# Salida.net
KiCad netlist of a schematic drawn in Altium Designer
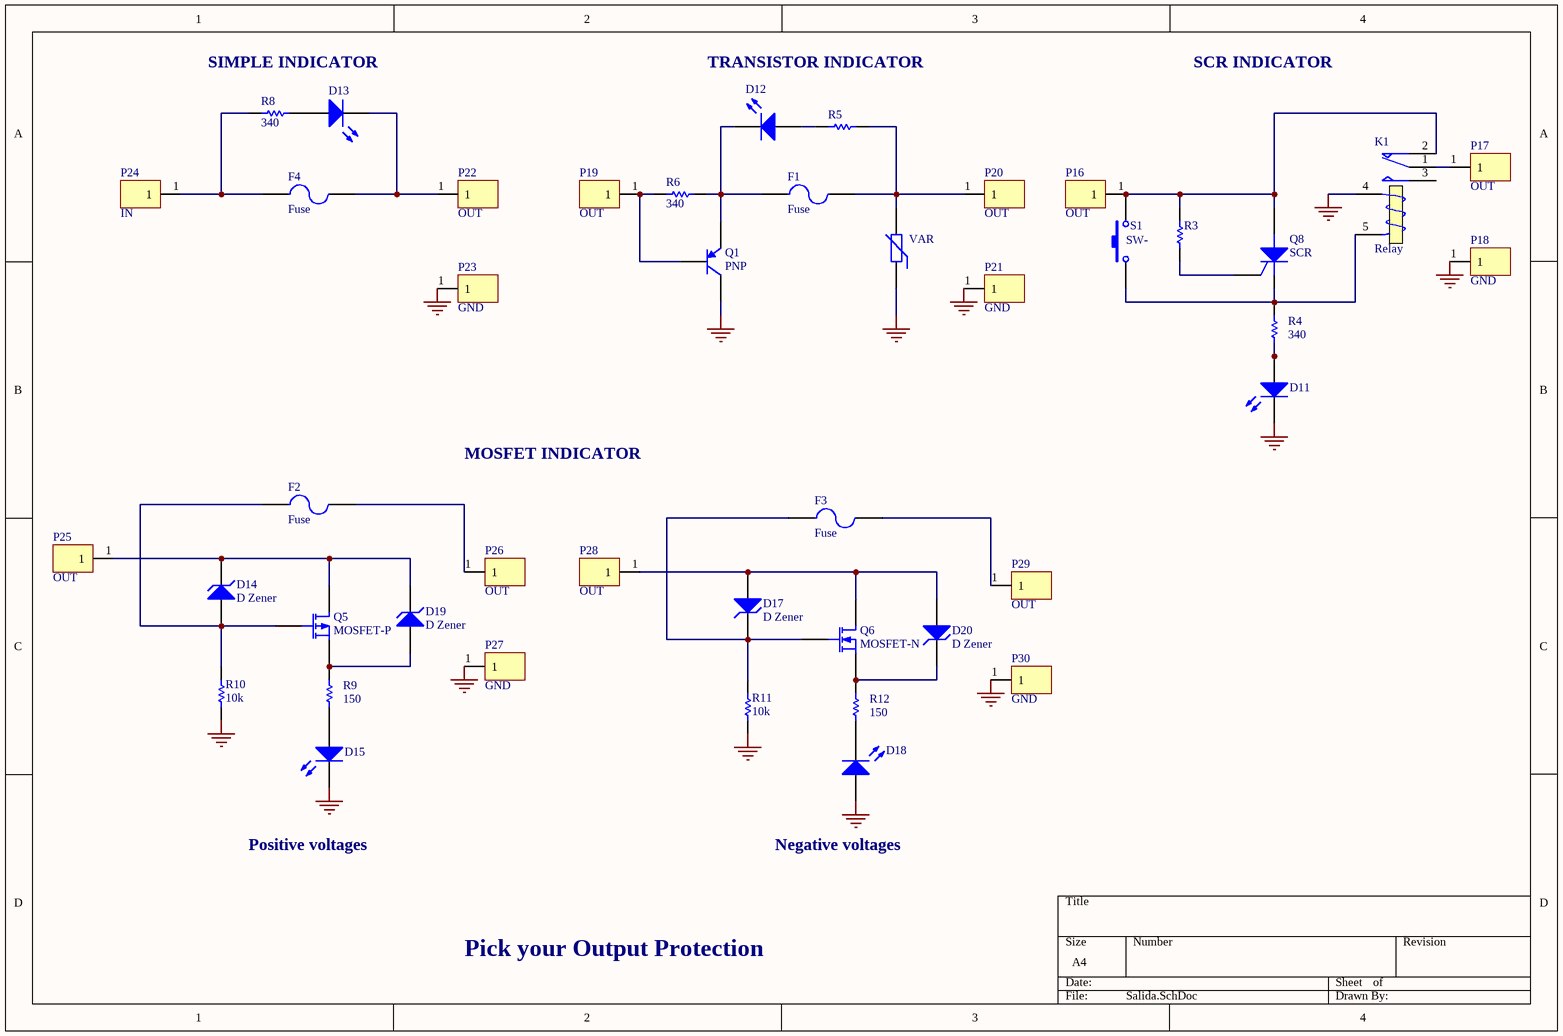
[diagram p0: Salida.SchDoc]

(export (version "E")
  (design (tool "Eeschema 10.0.6"))
  (components
    (comp (ref "D11")
      (value "LED0")
      (footprint "LED-0")
      (description "Typical INFRARED GaAs LED")
      (fields (field (name "PUBLISHER") "Altium Limited"))
      (libsource (lib "Miscellaneous Devices") (part "LED0"))
    )
    (comp (ref "D12")
      (value "LED0")
      (footprint "LED-0")
      (description "Typical INFRARED GaAs LED")
      (fields (field (name "PUBLISHER") "Altium Limited"))
      (libsource (lib "Miscellaneous Devices") (part "LED0"))
    )
    (comp (ref "D13")
      (value "LED0")
      (footprint "LED-0")
      (description "Typical INFRARED GaAs LED")
      (fields (field (name "PUBLISHER") "Altium Limited"))
      (libsource (lib "Miscellaneous Devices") (part "LED0"))
    )
    (comp (ref "D14")
      (value "D Zener")
      (footprint "DIODE-0.7")
      (description "Zener Diode")
      (fields (field (name "PUBLISHER") "Altium Limited"))
      (libsource (lib "Miscellaneous Devices") (part "D Zener"))
    )
    (comp (ref "D15")
      (value "LED0")
      (footprint "LED-0")
      (description "Typical INFRARED GaAs LED")
      (fields (field (name "PUBLISHER") "Altium Limited"))
      (libsource (lib "Miscellaneous Devices") (part "LED0"))
    )
    (comp (ref "D17")
      (value "D Zener")
      (footprint "DIODE-0.7")
      (description "Zener Diode")
      (fields (field (name "PUBLISHER") "Altium Limited"))
      (libsource (lib "Miscellaneous Devices") (part "D Zener"))
    )
    (comp (ref "D18")
      (value "LED0")
      (footprint "LED-0")
      (description "Typical INFRARED GaAs LED")
      (fields (field (name "PUBLISHER") "Altium Limited"))
      (libsource (lib "Miscellaneous Devices") (part "LED0"))
    )
    (comp (ref "D19")
      (value "D Zener")
      (footprint "DIODE-0.7")
      (description "Zener Diode")
      (fields (field (name "PUBLISHER") "Altium Limited"))
      (libsource (lib "Miscellaneous Devices") (part "D Zener"))
    )
    (comp (ref "D20")
      (value "D Zener")
      (footprint "DIODE-0.7")
      (description "Zener Diode")
      (fields (field (name "PUBLISHER") "Altium Limited"))
      (libsource (lib "Miscellaneous Devices") (part "D Zener"))
    )
    (comp (ref "F1")
      (value "Fuse")
      (footprint "PIN-W2/E2.8")
      (fields (field (name "PUBLISHER") "Altium Limited"))
      (libsource (lib "Miscellaneous Devices") (part "Fuse 2"))
    )
    (comp (ref "F2")
      (value "Fuse")
      (footprint "PIN-W2/E2.8")
      (fields (field (name "PUBLISHER") "Altium Limited"))
      (libsource (lib "Miscellaneous Devices") (part "Fuse 2"))
    )
    (comp (ref "F3")
      (value "Fuse")
      (footprint "PIN-W2/E2.8")
      (fields (field (name "PUBLISHER") "Altium Limited"))
      (libsource (lib "Miscellaneous Devices") (part "Fuse 2"))
    )
    (comp (ref "F4")
      (value "Fuse")
      (footprint "PIN-W2/E2.8")
      (fields (field (name "PUBLISHER") "Altium Limited"))
      (libsource (lib "Miscellaneous Devices") (part "Fuse 2"))
    )
    (comp (ref "K1")
      (value "Relay")
      (footprint "MODULE5B")
      (description "SPDT Relay")
      (fields (field (name "PUBLISHER") "Altium Limited"))
      (libsource (lib "Miscellaneous Devices") (part "Relay"))
    )
    (comp (ref "P16") (value "OUT") (footprint "cONECTOR") (libsource (lib "Conector") (part "Component_1")))
    (comp (ref "P17") (value "OUT") (footprint "cONECTOR") (libsource (lib "") (part "Component_1_1")))
    (comp (ref "P18") (value "GND") (footprint "cONECTOR") (libsource (lib "") (part "Component_1_1")))
    (comp (ref "P19") (value "OUT") (footprint "cONECTOR") (libsource (lib "Conector") (part "Component_1")))
    (comp (ref "P20") (value "OUT") (footprint "cONECTOR") (libsource (lib "") (part "Component_1_1")))
    (comp (ref "P21") (value "GND") (footprint "cONECTOR") (libsource (lib "") (part "Component_1_1")))
    (comp (ref "P22") (value "OUT") (footprint "cONECTOR") (libsource (lib "") (part "Component_1_1")))
    (comp (ref "P23") (value "GND") (footprint "cONECTOR") (libsource (lib "") (part "Component_1_1")))
    (comp (ref "P24") (value "IN") (footprint "cONECTOR") (libsource (lib "Conector") (part "Component_1")))
    (comp (ref "P25") (value "OUT") (footprint "cONECTOR") (libsource (lib "Conector") (part "Component_1")))
    (comp (ref "P26") (value "OUT") (footprint "cONECTOR") (libsource (lib "") (part "Component_1_1")))
    (comp (ref "P27") (value "GND") (footprint "cONECTOR") (libsource (lib "") (part "Component_1_1")))
    (comp (ref "P28") (value "OUT") (footprint "cONECTOR") (libsource (lib "Conector") (part "Component_1")))
    (comp (ref "P29") (value "OUT") (footprint "cONECTOR") (libsource (lib "") (part "Component_1_1")))
    (comp (ref "P30") (value "GND") (footprint "cONECTOR") (libsource (lib "") (part "Component_1_1")))
    (comp (ref "Q1")
      (value "PNP")
      (footprint "SOT-23B_N")
      (description "PNP Bipolar Transistor")
      (fields (field (name "PUBLISHER") "Altium Limited"))
      (libsource (lib "Miscellaneous Devices") (part "PNP"))
    )
    (comp (ref "Q5")
      (value "MOSFET-P")
      (footprint "E3")
      (description "P-Channel MOSFET")
      (fields (field (name "PUBLISHER") "Altium Limited"))
      (libsource (lib "Miscellaneous Devices") (part "MOSFET-P"))
    )
    (comp (ref "Q6")
      (value "MOSFET-N")
      (footprint "E3")
      (description "N-Channel MOSFET")
      (fields (field (name "PUBLISHER") "Altium Limited"))
      (libsource (lib "Miscellaneous Devices") (part "MOSFET-N"))
    )
    (comp (ref "Q8")
      (value "SCR")
      (footprint "TO-220-AB")
      (description "Silicon Controlled Rectifier")
      (fields (field (name "PUBLISHER") "Altium Limited"))
      (libsource (lib "Miscellaneous Devices") (part "SCR"))
    )
    (comp (ref "R3")
      (value "Res1")
      (footprint "AXIAL-0.3")
      (description "Resistor")
      (fields (field (name "PUBLISHER") "Altium Limited"))
      (libsource (lib "Miscellaneous Devices") (part "Res1"))
    )
    (comp (ref "R4")
      (value "340")
      (footprint "AXIAL-0.3")
      (description "Resistor")
      (fields (field (name "PUBLISHER") "Altium Limited"))
      (libsource (lib "Miscellaneous Devices") (part "Res1"))
    )
    (comp (ref "R5")
      (value "340")
      (footprint "AXIAL-0.3")
      (description "Resistor")
      (fields (field (name "PUBLISHER") "Altium Limited"))
      (libsource (lib "Miscellaneous Devices") (part "Res1"))
    )
    (comp (ref "R6")
      (value "340")
      (footprint "AXIAL-0.3")
      (description "Resistor")
      (fields (field (name "PUBLISHER") "Altium Limited"))
      (libsource (lib "Miscellaneous Devices") (part "Res1"))
    )
    (comp (ref "R8")
      (value "340")
      (footprint "AXIAL-0.3")
      (description "Resistor")
      (fields (field (name "PUBLISHER") "Altium Limited"))
      (libsource (lib "Miscellaneous Devices") (part "Res1"))
    )
    (comp (ref "R9")
      (value "150")
      (footprint "AXIAL-0.3")
      (description "Resistor")
      (fields (field (name "PUBLISHER") "Altium Limited"))
      (libsource (lib "Miscellaneous Devices") (part "Res1"))
    )
    (comp (ref "R10")
      (value "10k")
      (footprint "AXIAL-0.3")
      (description "Resistor")
      (fields (field (name "PUBLISHER") "Altium Limited"))
      (libsource (lib "Miscellaneous Devices") (part "Res1"))
    )
    (comp (ref "R11")
      (value "10k")
      (footprint "AXIAL-0.3")
      (description "Resistor")
      (fields (field (name "PUBLISHER") "Altium Limited"))
      (libsource (lib "Miscellaneous Devices") (part "Res1"))
    )
    (comp (ref "R12")
      (value "150")
      (footprint "AXIAL-0.3")
      (description "Resistor")
      (fields (field (name "PUBLISHER") "Altium Limited"))
      (libsource (lib "Miscellaneous Devices") (part "Res1"))
    )
    (comp (ref "S1")
      (value "SW-")
      (footprint "SPST-2")
      (description "Switch")
      (fields (field (name "PUBLISHER") "Altium Limited"))
      (libsource (lib "Miscellaneous Devices") (part "SW-PB"))
    )
    (comp (ref "VAR")
      (value "Res Varistor")
      (footprint "6-0805_N")
      (description "Varistor (Voltage-Sensitive Resistor)")
      (fields (field (name "PUBLISHER") "Altium Limited"))
      (libsource (lib "Miscellaneous Devices") (part "Res Varistor"))
    )
  )
  (nets
    (net (code "1") (name "GND") (class "Default")
      (node (ref "D11") (pin "2") (pinfunction "K_2") (pintype "passive"))
      (node (ref "D15") (pin "2") (pinfunction "K_2") (pintype "passive"))
      (node (ref "D18") (pin "1") (pinfunction "A_1") (pintype "passive"))
      (node (ref "K1") (pin "4") (pinfunction "T1_4") (pintype "passive"))
      (node (ref "P18") (pin "1") (pinfunction "1_1") (pintype "passive"))
      (node (ref "P21") (pin "1") (pinfunction "1_1") (pintype "passive"))
      (node (ref "P23") (pin "1") (pinfunction "1_1") (pintype "passive"))
      (node (ref "P27") (pin "1") (pinfunction "1_1") (pintype "passive"))
      (node (ref "P30") (pin "1") (pinfunction "1_1") (pintype "passive"))
      (node (ref "Q1") (pin "1") (pinfunction "C_1") (pintype "passive"))
      (node (ref "R10") (pin "1") (pinfunction "1_1") (pintype "passive"))
      (node (ref "R11") (pin "1") (pinfunction "1_1") (pintype "passive"))
      (node (ref "VAR") (pin "1") (pinfunction "1_1") (pintype "passive"))
    )
    (net (code "2") (name "Net-(D11-A)") (class "Default")
      (node (ref "D11") (pin "1") (pinfunction "A_1") (pintype "passive"))
      (node (ref "R4") (pin "1") (pinfunction "1_1") (pintype "passive"))
    )
    (net (code "3") (name "Net-(D12-A)") (class "Default")
      (node (ref "D12") (pin "1") (pinfunction "A_1") (pintype "passive"))
      (node (ref "R5") (pin "1") (pinfunction "1_1") (pintype "passive"))
    )
    (net (code "4") (name "Net-(D12-K)") (class "Default")
      (node (ref "D12") (pin "2") (pinfunction "K_2") (pintype "passive"))
      (node (ref "F1") (pin "1") (pinfunction "1_1") (pintype "passive"))
      (node (ref "Q1") (pin "3") (pinfunction "E_3") (pintype "passive"))
      (node (ref "R6") (pin "2") (pinfunction "2_2") (pintype "passive"))
    )
    (net (code "5") (name "Net-(D13-A)") (class "Default")
      (node (ref "D13") (pin "1") (pinfunction "A_1") (pintype "passive"))
      (node (ref "R8") (pin "1") (pinfunction "1_1") (pintype "passive"))
    )
    (net (code "6") (name "Net-(D13-K)") (class "Default")
      (node (ref "D13") (pin "2") (pinfunction "K_2") (pintype "passive"))
      (node (ref "F4") (pin "2") (pinfunction "2_2") (pintype "passive"))
      (node (ref "P22") (pin "1") (pinfunction "1_1") (pintype "passive"))
    )
    (net (code "7") (name "Net-(D14-A)") (class "Default")
      (node (ref "D14") (pin "1") (pinfunction "A_1") (pintype "passive"))
      (node (ref "F2") (pin "1") (pinfunction "1_1") (pintype "passive"))
      (node (ref "Q5") (pin "2") (pinfunction "G_2") (pintype "passive"))
      (node (ref "R10") (pin "2") (pinfunction "2_2") (pintype "passive"))
    )
    (net (code "8") (name "Net-(D14-K)") (class "Default")
      (node (ref "D14") (pin "2") (pinfunction "K_2") (pintype "passive"))
      (node (ref "D19") (pin "2") (pinfunction "K_2") (pintype "passive"))
      (node (ref "P25") (pin "1") (pinfunction "1_1") (pintype "passive"))
      (node (ref "Q5") (pin "1") (pinfunction "D_1") (pintype "passive"))
    )
    (net (code "9") (name "Net-(D15-A)") (class "Default")
      (node (ref "D15") (pin "1") (pinfunction "A_1") (pintype "passive"))
      (node (ref "R9") (pin "1") (pinfunction "1_1") (pintype "passive"))
    )
    (net (code "10") (name "Net-(D17-A)") (class "Default")
      (node (ref "D17") (pin "1") (pinfunction "A_1") (pintype "passive"))
      (node (ref "D20") (pin "1") (pinfunction "A_1") (pintype "passive"))
      (node (ref "P28") (pin "1") (pinfunction "1_1") (pintype "passive"))
      (node (ref "Q6") (pin "1") (pinfunction "D_1") (pintype "passive"))
    )
    (net (code "11") (name "Net-(D17-K)") (class "Default")
      (node (ref "D17") (pin "2") (pinfunction "K_2") (pintype "passive"))
      (node (ref "F3") (pin "1") (pinfunction "1_1") (pintype "passive"))
      (node (ref "Q6") (pin "2") (pinfunction "G_2") (pintype "passive"))
      (node (ref "R11") (pin "2") (pinfunction "2_2") (pintype "passive"))
    )
    (net (code "12") (name "Net-(D18-K)") (class "Default")
      (node (ref "D18") (pin "2") (pinfunction "K_2") (pintype "passive"))
      (node (ref "R12") (pin "1") (pinfunction "1_1") (pintype "passive"))
    )
    (net (code "13") (name "Net-(D19-A)") (class "Default")
      (node (ref "D19") (pin "1") (pinfunction "A_1") (pintype "passive"))
      (node (ref "Q5") (pin "3") (pinfunction "S_3") (pintype "passive"))
      (node (ref "R9") (pin "2") (pinfunction "2_2") (pintype "passive"))
    )
    (net (code "14") (name "Net-(D20-K)") (class "Default")
      (node (ref "D20") (pin "2") (pinfunction "K_2") (pintype "passive"))
      (node (ref "Q6") (pin "3") (pinfunction "S_3") (pintype "passive"))
      (node (ref "R12") (pin "2") (pinfunction "2_2") (pintype "passive"))
    )
    (net (code "15") (name "Net-(F1-Pad2)") (class "Default")
      (node (ref "F1") (pin "2") (pinfunction "2_2") (pintype "passive"))
      (node (ref "P20") (pin "1") (pinfunction "1_1") (pintype "passive"))
      (node (ref "R5") (pin "2") (pinfunction "2_2") (pintype "passive"))
      (node (ref "VAR") (pin "2") (pinfunction "2_2") (pintype "passive"))
    )
    (net (code "16") (name "Net-(F2-Pad2)") (class "Default")
      (node (ref "F2") (pin "2") (pinfunction "2_2") (pintype "passive"))
      (node (ref "P26") (pin "1") (pinfunction "1_1") (pintype "passive"))
    )
    (net (code "17") (name "Net-(F3-Pad2)") (class "Default")
      (node (ref "F3") (pin "2") (pinfunction "2_2") (pintype "passive"))
      (node (ref "P29") (pin "1") (pinfunction "1_1") (pintype "passive"))
    )
    (net (code "18") (name "Net-(F4-Pad1)") (class "Default")
      (node (ref "F4") (pin "1") (pinfunction "1_1") (pintype "passive"))
      (node (ref "P24") (pin "1") (pinfunction "1_1") (pintype "passive"))
      (node (ref "R8") (pin "2") (pinfunction "2_2") (pintype "passive"))
    )
    (net (code "19") (name "Net-(K1-COM)") (class "Default")
      (node (ref "K1") (pin "1") (pinfunction "COM_1") (pintype "passive"))
      (node (ref "P17") (pin "1") (pinfunction "1_1") (pintype "passive"))
    )
    (net (code "20") (name "Net-(K1-NC)") (class "Default")
      (node (ref "K1") (pin "2") (pinfunction "NC_2") (pintype "passive"))
      (node (ref "P16") (pin "1") (pinfunction "1_1") (pintype "passive"))
      (node (ref "Q8") (pin "1") (pinfunction "A_1") (pintype "passive"))
      (node (ref "R3") (pin "2") (pinfunction "2_2") (pintype "passive"))
      (node (ref "S1") (pin "2") (pinfunction "2_2") (pintype "passive"))
    )
    (net (code "21") (name "Net-(K1-T2)") (class "Default")
      (node (ref "K1") (pin "5") (pinfunction "T2_5") (pintype "passive"))
      (node (ref "Q8") (pin "3") (pinfunction "K_3") (pintype "passive"))
      (node (ref "R4") (pin "2") (pinfunction "2_2") (pintype "passive"))
      (node (ref "S1") (pin "1") (pinfunction "1_1") (pintype "passive"))
    )
    (net (code "22") (name "Net-(Q1-B)") (class "Default")
      (node (ref "P19") (pin "1") (pinfunction "1_1") (pintype "passive"))
      (node (ref "Q1") (pin "2") (pinfunction "B_2") (pintype "passive"))
      (node (ref "R6") (pin "1") (pinfunction "1_1") (pintype "passive"))
    )
    (net (code "23") (name "Net-(Q8-G)") (class "Default")
      (node (ref "Q8") (pin "2") (pinfunction "G_2") (pintype "passive"))
      (node (ref "R3") (pin "1") (pinfunction "1_1") (pintype "passive"))
    )
    (net (code "24") (name "unconnected-(K1-NO-Pad3)") (class "Default")
      (node (ref "K1") (pin "3") (pinfunction "NO_3") (pintype "passive"))
    )
  )
)
